# Adafruit_LSM6DSOX.net
KiCad netlist of a schematic drawn in EAGLE
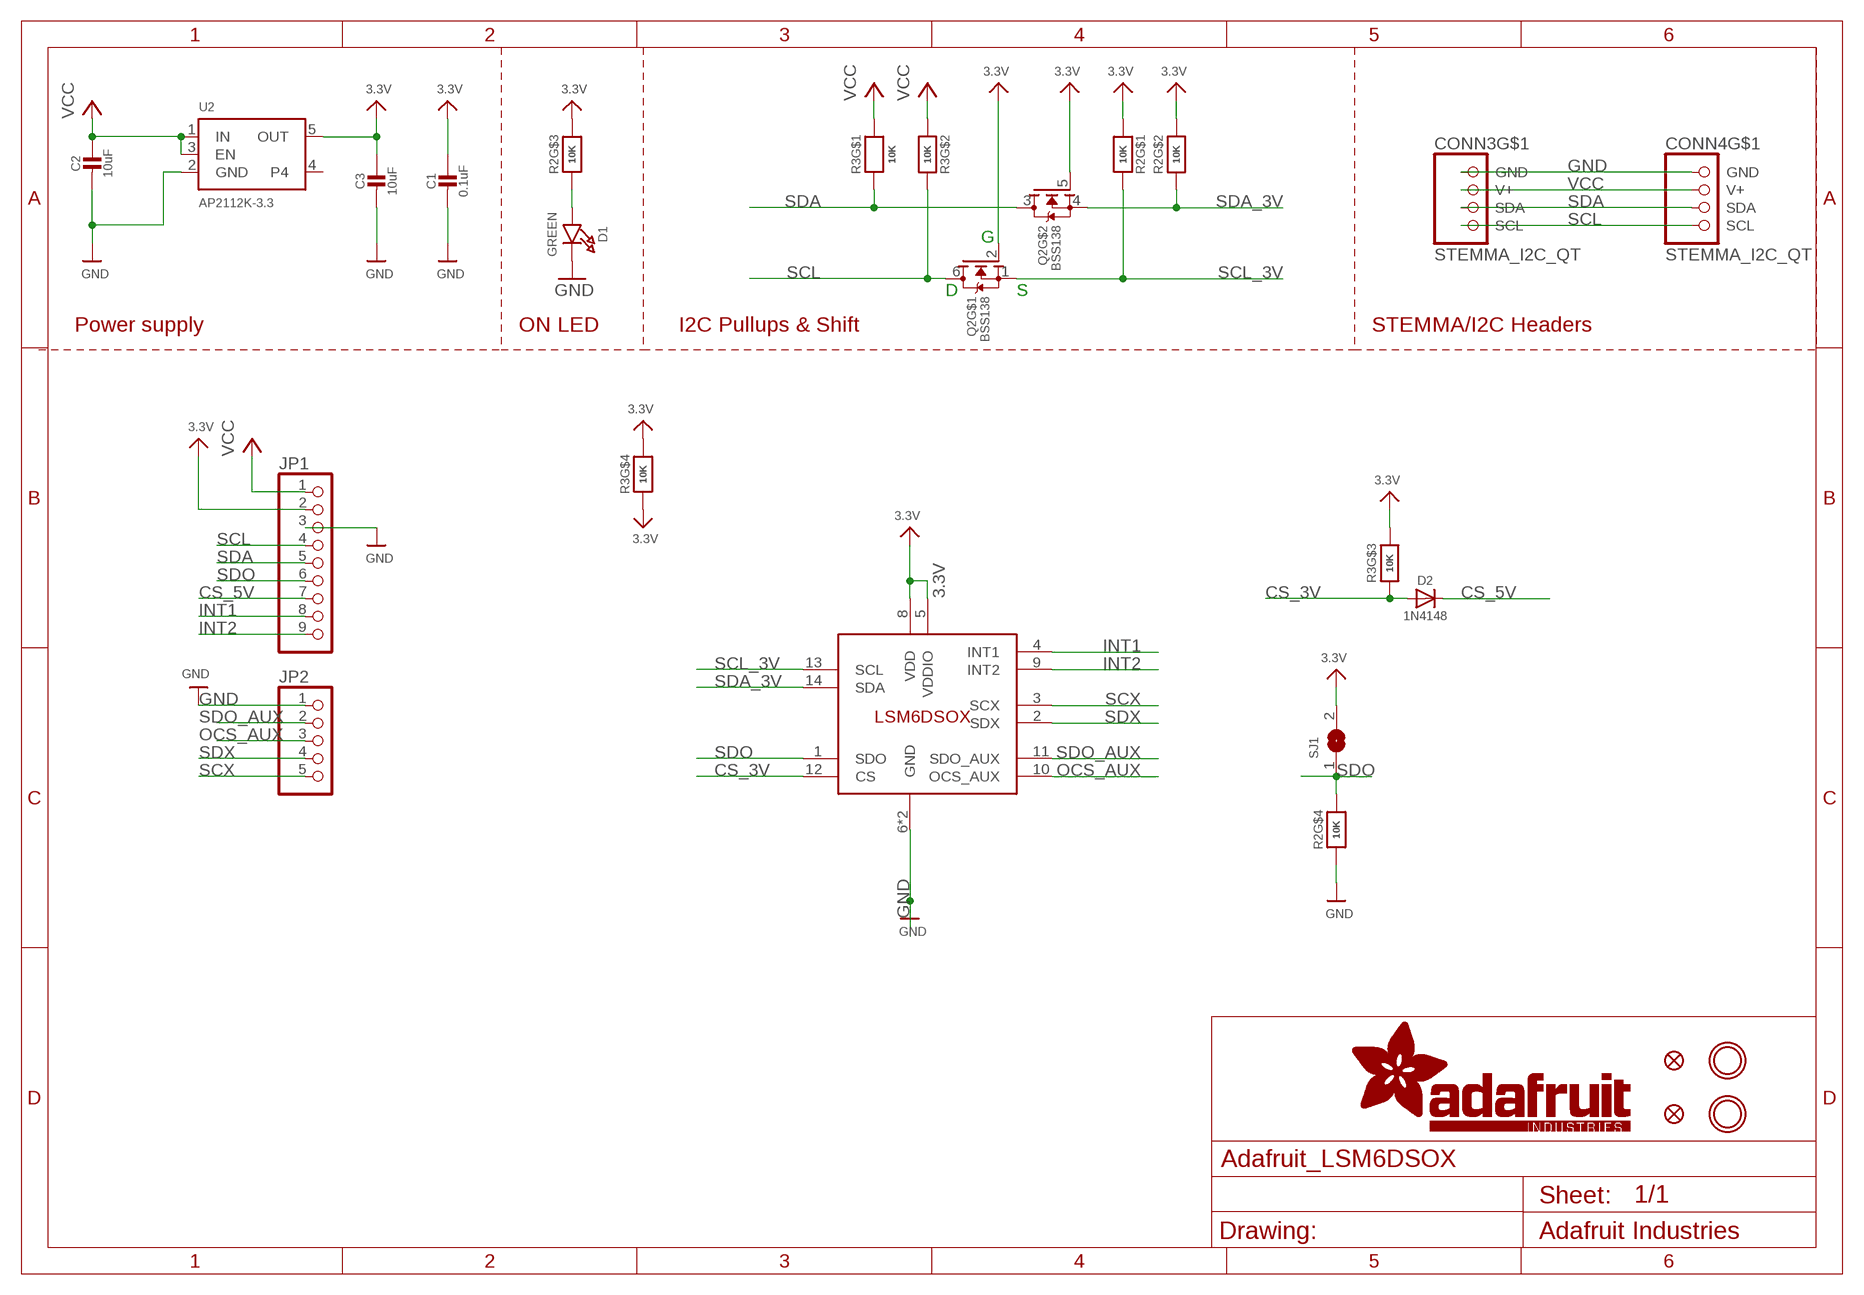
[diagram p0: schematic, sheet 1]

(export (version "E")
  (design (tool "Eeschema 10.0.6"))
  (components
    (comp (ref "C1")
      (value "0.1uF")
      (footprint "eagle-import:0603-NO")
      (libsource (lib "eagle-import") (part "CAP_CERAMIC0603_NO"))
    )
    (comp (ref "C2")
      (value "10uF")
      (footprint "eagle-import:0805-NO")
      (libsource (lib "eagle-import") (part "CAP_CERAMIC0805-NOOUTLINE"))
    )
    (comp (ref "C3")
      (value "10uF")
      (footprint "eagle-import:0805-NO")
      (libsource (lib "eagle-import") (part "CAP_CERAMIC0805-NOOUTLINE"))
    )
    (comp (ref "CONN3")
      (value "STEMMA_I2C_QT")
      (footprint "eagle-import:JST_SH4")
      (libsource (lib "eagle-import") (part "STEMMA_I2C_QT"))
    )
    (comp (ref "CONN4")
      (value "STEMMA_I2C_QT")
      (footprint "eagle-import:JST_SH4")
      (libsource (lib "eagle-import") (part "STEMMA_I2C_QT"))
    )
    (comp (ref "D1")
      (value "GREEN")
      (footprint "eagle-import:CHIPLED_0603_NOOUTLINE")
      (libsource (lib "eagle-import") (part "LED0603_NOOUTLINE"))
    )
    (comp (ref "D2")
      (value "1N4148")
      (footprint "eagle-import:SOD-323")
      (libsource (lib "eagle-import") (part "DIODESOD-323"))
    )
    (comp (ref "FID3")
      (value "FIDUCIAL_1MM")
      (footprint "eagle-import:FIDUCIAL_1MM")
      (libsource (lib "eagle-import") (part "FIDUCIAL_1MM"))
    )
    (comp (ref "FID4")
      (value "FIDUCIAL_1MM")
      (footprint "eagle-import:FIDUCIAL_1MM")
      (libsource (lib "eagle-import") (part "FIDUCIAL_1MM"))
    )
    (comp (ref "JP1")
      (value "HEADER-1X970MIL")
      (footprint "eagle-import:1X09_ROUND_70")
      (libsource (lib "eagle-import") (part "HEADER-1X970MIL"))
    )
    (comp (ref "JP2")
      (value "HEADER-1X570MIL")
      (footprint "eagle-import:1X05_ROUND_70")
      (libsource (lib "eagle-import") (part "HEADER-1X570MIL"))
    )
    (comp (ref "Q2")
      (value "BSS138")
      (footprint "eagle-import:SOT363")
      (libsource (lib "eagle-import") (part "MOSFET-N_DUAL"))
    )
    (comp (ref "R2")
      (value "10K")
      (footprint "eagle-import:RESPACK_4X0603")
      (libsource (lib "eagle-import") (part "RESISTOR_4PACK"))
    )
    (comp (ref "R3")
      (value "10K")
      (footprint "eagle-import:RESPACK_4X0603")
      (libsource (lib "eagle-import") (part "RESISTOR_4PACK"))
    )
    (comp (ref "SJ1")
      (value "SOLDERJUMPER")
      (footprint "eagle-import:SOLDERJUMPER_ARROW_NOPASTE")
      (libsource (lib "eagle-import") (part "SOLDERJUMPER"))
    )
    (comp (ref "U$1")
      (value "MOUNTINGHOLE2.5")
      (footprint "eagle-import:MOUNTINGHOLE_2.5_PLATED")
      (libsource (lib "eagle-import") (part "MOUNTINGHOLE2.5"))
    )
    (comp (ref "U$2")
      (value "LSM6DSOX")
      (footprint "eagle-import:LGA-14L")
      (libsource (lib "eagle-import") (part "LSM6DSOX"))
    )
    (comp (ref "U$17")
      (value "MOUNTINGHOLE2.5")
      (footprint "eagle-import:MOUNTINGHOLE_2.5_PLATED")
      (libsource (lib "eagle-import") (part "MOUNTINGHOLE2.5"))
    )
    (comp (ref "U2")
      (value "AP2112K-3.3")
      (footprint "eagle-import:SOT23-5")
      (libsource (lib "eagle-import") (part "VREG_SOT23-5"))
    )
  )
  (nets
    (net (code "1") (name "/CS_3V") (class "Default")
      (node (ref "D2") (pin "A") (pinfunction "A_A") (pintype "passive"))
      (node (ref "R3") (pin "6") (pinfunction "2_6") (pintype "passive"))
      (node (ref "U$2") (pin "12") (pinfunction "CS_12") (pintype "bidirectional"))
    )
    (net (code "2") (name "/CS_5V") (class "Default")
      (node (ref "D2") (pin "C") (pinfunction "C_C") (pintype "passive"))
      (node (ref "JP1") (pin "7") (pinfunction "7_7") (pintype "passive"))
    )
    (net (code "3") (name "/INT1") (class "Default")
      (node (ref "JP1") (pin "8") (pinfunction "8_8") (pintype "passive"))
      (node (ref "U$2") (pin "4") (pinfunction "INT1_4") (pintype "bidirectional"))
    )
    (net (code "4") (name "/INT2") (class "Default")
      (node (ref "JP1") (pin "9") (pinfunction "9_9") (pintype "passive"))
      (node (ref "U$2") (pin "9") (pinfunction "INT2_9") (pintype "bidirectional"))
    )
    (net (code "5") (name "/OCS_AUX") (class "Default")
      (node (ref "JP2") (pin "3") (pinfunction "3_3") (pintype "passive"))
      (node (ref "U$2") (pin "10") (pinfunction "OCS_AUX_10") (pintype "bidirectional"))
    )
    (net (code "6") (name "/SCL") (class "Default")
      (node (ref "CONN3") (pin "4") (pinfunction "SCL_4") (pintype "passive"))
      (node (ref "CONN4") (pin "4") (pinfunction "SCL_4") (pintype "passive"))
      (node (ref "JP1") (pin "4") (pinfunction "4_4") (pintype "passive"))
      (node (ref "Q2") (pin "6") (pinfunction "D_6") (pintype "bidirectional"))
      (node (ref "R3") (pin "2") (pinfunction "1_2") (pintype "passive"))
    )
    (net (code "7") (name "/SCL_3V") (class "Default")
      (node (ref "Q2") (pin "1") (pinfunction "S_1") (pintype "bidirectional"))
      (node (ref "R2") (pin "8") (pinfunction "2_8") (pintype "passive"))
      (node (ref "U$2") (pin "13") (pinfunction "SCL_13") (pintype "bidirectional"))
    )
    (net (code "8") (name "/SCX") (class "Default")
      (node (ref "JP2") (pin "5") (pinfunction "5_5") (pintype "passive"))
      (node (ref "U$2") (pin "3") (pinfunction "SCX_3") (pintype "bidirectional"))
    )
    (net (code "9") (name "/SDA") (class "Default")
      (node (ref "CONN3") (pin "3") (pinfunction "SDA_3") (pintype "passive"))
      (node (ref "CONN4") (pin "3") (pinfunction "SDA_3") (pintype "passive"))
      (node (ref "JP1") (pin "5") (pinfunction "5_5") (pintype "passive"))
      (node (ref "Q2") (pin "3") (pinfunction "D_3") (pintype "bidirectional"))
      (node (ref "R3") (pin "1") (pinfunction "1_1") (pintype "passive"))
    )
    (net (code "10") (name "/SDA_3V") (class "Default")
      (node (ref "Q2") (pin "4") (pinfunction "S_4") (pintype "bidirectional"))
      (node (ref "R2") (pin "7") (pinfunction "2_7") (pintype "passive"))
      (node (ref "U$2") (pin "14") (pinfunction "SDA_14") (pintype "bidirectional"))
    )
    (net (code "11") (name "/SDO") (class "Default")
      (node (ref "JP1") (pin "6") (pinfunction "6_6") (pintype "passive"))
      (node (ref "R2") (pin "5") (pinfunction "2_5") (pintype "passive"))
      (node (ref "SJ1") (pin "1") (pinfunction "1_1") (pintype "passive"))
      (node (ref "U$2") (pin "1") (pinfunction "SDO_1") (pintype "bidirectional"))
    )
    (net (code "12") (name "/SDO_AUX") (class "Default")
      (node (ref "JP2") (pin "2") (pinfunction "2_2") (pintype "passive"))
      (node (ref "U$2") (pin "11") (pinfunction "SDO_AUX_11") (pintype "bidirectional"))
    )
    (net (code "13") (name "/SDX") (class "Default")
      (node (ref "JP2") (pin "4") (pinfunction "4_4") (pintype "passive"))
      (node (ref "U$2") (pin "2") (pinfunction "SDX_2") (pintype "bidirectional"))
    )
    (net (code "14") (name "3.3V") (class "Default")
      (node (ref "C1") (pin "1") (pinfunction "1_1") (pintype "passive"))
      (node (ref "C3") (pin "1") (pinfunction "1_1") (pintype "passive"))
      (node (ref "JP1") (pin "2") (pinfunction "2_2") (pintype "passive"))
      (node (ref "Q2") (pin "2") (pinfunction "G_2") (pintype "bidirectional"))
      (node (ref "Q2") (pin "5") (pinfunction "G_5") (pintype "bidirectional"))
      (node (ref "R2") (pin "1") (pinfunction "1_1") (pintype "passive"))
      (node (ref "R2") (pin "2") (pinfunction "1_2") (pintype "passive"))
      (node (ref "R2") (pin "6") (pinfunction "2_6") (pintype "passive"))
      (node (ref "R3") (pin "3") (pinfunction "1_3") (pintype "passive"))
      (node (ref "R3") (pin "4") (pinfunction "1_4") (pintype "passive"))
      (node (ref "R3") (pin "5") (pinfunction "2_5") (pintype "passive"))
      (node (ref "SJ1") (pin "2") (pinfunction "2_2") (pintype "passive"))
      (node (ref "U$2") (pin "5") (pinfunction "VDDIO_5") (pintype "power_in"))
      (node (ref "U$2") (pin "8") (pinfunction "VDD_8") (pintype "power_in"))
      (node (ref "U2") (pin "5") (pinfunction "OUT_5") (pintype "power_in"))
    )
    (net (code "15") (name "GND") (class "Default")
      (node (ref "C1") (pin "2") (pinfunction "2_2") (pintype "passive"))
      (node (ref "C2") (pin "2") (pinfunction "2_2") (pintype "passive"))
      (node (ref "C3") (pin "2") (pinfunction "2_2") (pintype "passive"))
      (node (ref "CONN3") (pin "1") (pinfunction "GND_1") (pintype "passive"))
      (node (ref "CONN4") (pin "1") (pinfunction "GND_1") (pintype "passive"))
      (node (ref "D1") (pin "C") (pinfunction "C_C") (pintype "passive"))
      (node (ref "JP1") (pin "3") (pinfunction "3_3") (pintype "passive"))
      (node (ref "JP2") (pin "1") (pinfunction "1_1") (pintype "passive"))
      (node (ref "R2") (pin "4") (pinfunction "1_4") (pintype "passive"))
      (node (ref "U$2") (pin "6") (pinfunction "GND_6") (pintype "power_in"))
      (node (ref "U$2") (pin "7") (pinfunction "GND_7") (pintype "power_in"))
      (node (ref "U2") (pin "2") (pinfunction "GND_2") (pintype "power_in"))
    )
    (net (code "16") (name "Net-(R2C-1)") (class "Default")
      (node (ref "D1") (pin "A") (pinfunction "A_A") (pintype "passive"))
      (node (ref "R2") (pin "3") (pinfunction "1_3") (pintype "passive"))
    )
    (net (code "17") (name "VCC") (class "Default")
      (node (ref "C2") (pin "1") (pinfunction "1_1") (pintype "passive"))
      (node (ref "CONN3") (pin "2") (pinfunction "V+_2") (pintype "passive"))
      (node (ref "CONN4") (pin "2") (pinfunction "V+_2") (pintype "passive"))
      (node (ref "JP1") (pin "1") (pinfunction "1_1") (pintype "passive"))
      (node (ref "R3") (pin "7") (pinfunction "2_7") (pintype "passive"))
      (node (ref "R3") (pin "8") (pinfunction "2_8") (pintype "passive"))
      (node (ref "U2") (pin "1") (pinfunction "IN_1") (pintype "power_in"))
      (node (ref "U2") (pin "3") (pinfunction "EN_3") (pintype "input"))
    )
    (net (code "18") (name "unconnected-(U2-P4-Pad4)") (class "Default")
      (node (ref "U2") (pin "4") (pinfunction "P4_4") (pintype "bidirectional"))
    )
  )
)
